# MISC.net
KiCad netlist of a schematic drawn in Altium Designer
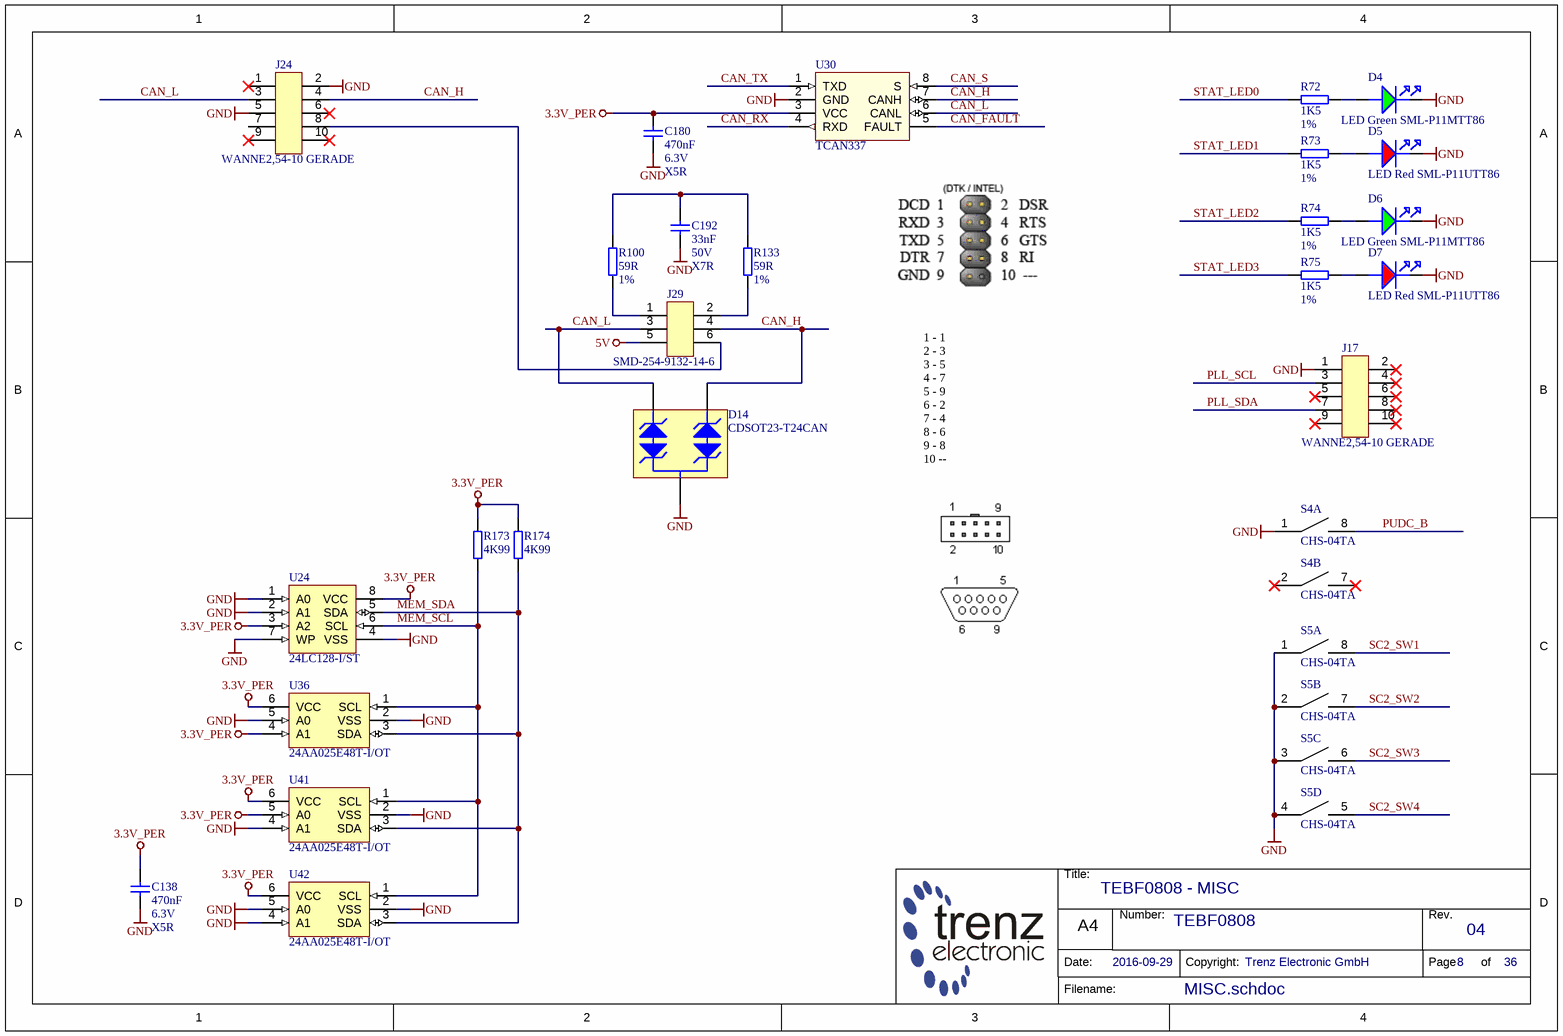
[diagram p0: MISC.schdoc]

(export (version "E")
  (design (tool "Eeschema 10.0.6"))
  (components
    (comp (ref "C138")
      (value "470nF")
      (footprint "CAPC1005X55N")
      (description "KON 470nF 6,3V X5R SMD")
      (fields (field (name "VOLTAGE") "6.3V") (field (name "TECHNOLOGY") "X5R"))
      (libsource (lib "TE") (part "CAP-NP"))
    )
    (comp (ref "C180")
      (value "470nF")
      (footprint "CAPC1005X55N")
      (description "KON 470nF 6,3V X5R SMD")
      (fields (field (name "VOLTAGE") "6.3V") (field (name "TECHNOLOGY") "X5R"))
      (libsource (lib "TE") (part "CAP-NP"))
    )
    (comp (ref "C192")
      (value "33nF")
      (footprint "CAPC1608X90N")
      (description "KON 33nF 50V X7R SMD 10%")
      (fields
        (field (name "VOLTAGE") "50V")
        (field (name "TECHNOLOGY") "X7R")
        (field (name "TOLERANCE") "10%")
      )
      (libsource (lib "TE") (part "CAP-NP"))
    )
    (comp (ref "D4")
      (value "LED Green SML-P11MTT86")
      (footprint "LEDC1006X25N_GREEN")
      (description "LED Grün SML-P11MTT86 SMD")
      (libsource (lib "TE") (part "LED_GRUEN"))
    )
    (comp (ref "D5")
      (value "LED Red SML-P11UTT86")
      (footprint "LEDC1006X25N_RED")
      (description "LED Rot SML-P11UTT86 SMD")
      (libsource (lib "TE") (part "LED_ROT"))
    )
    (comp (ref "D6")
      (value "LED Green SML-P11MTT86")
      (footprint "LEDC1006X25N_GREEN")
      (description "LED Grün SML-P11MTT86 SMD")
      (libsource (lib "TE") (part "LED_GRUEN"))
    )
    (comp (ref "D7")
      (value "LED Red SML-P11UTT86")
      (footprint "LEDC1006X25N_RED")
      (description "LED Rot SML-P11UTT86 SMD")
      (libsource (lib "TE") (part "LED_ROT"))
    )
    (comp (ref "D14")
      (value "CDSOT23-T24CAN")
      (footprint "SOT95P237X112-3N")
      (libsource (lib "TE") (part "SM712"))
    )
    (comp (ref "J17")
      (value "WANNE2,54-10 GERADE")
      (footprint "WANNE2,54-10 GERADE")
      (description "Stiftleiste Wanne 10polig")
      (libsource (lib "TE") (part "CON-10"))
    )
    (comp (ref "J24")
      (value "WANNE2,54-10 GERADE")
      (footprint "WANNE2,54-10 GERADE")
      (description "Stiftleiste Wanne 10polig")
      (libsource (lib "TE") (part "CON-10"))
    )
    (comp (ref "J29")
      (value "SMD-254-9132-14-6")
      (footprint "SMD-254-9132-14-6")
      (description "Stiftleiste gerade 2-reihig, 6pol. SMD")
      (libsource (lib "TE") (part "CON-6"))
    )
    (comp (ref "R72")
      (value "1K5")
      (footprint "RESC1005X40N")
      (description "WID SMD 1K5 1% 0,063W")
      (fields (field (name "TOLERANCE") "1%"))
      (libsource (lib "TE") (part "RES"))
    )
    (comp (ref "R73")
      (value "1K5")
      (footprint "RESC1005X40N")
      (description "WID SMD 1K5 1% 0,063W")
      (fields (field (name "TOLERANCE") "1%"))
      (libsource (lib "TE") (part "RES"))
    )
    (comp (ref "R74")
      (value "1K5")
      (footprint "RESC1005X40N")
      (description "WID SMD 1K5 1% 0,063W")
      (fields (field (name "TOLERANCE") "1%"))
      (libsource (lib "TE") (part "RES"))
    )
    (comp (ref "R75")
      (value "1K5")
      (footprint "RESC1005X40N")
      (description "WID SMD 1K5 1% 0,063W")
      (fields (field (name "TOLERANCE") "1%"))
      (libsource (lib "TE") (part "RES"))
    )
    (comp (ref "R100")
      (value "59R")
      (footprint "RESC6332X80N")
      (description "WID SMD 59R 2W 1%")
      (fields (field (name "TOLERANCE") "1%"))
      (libsource (lib "TE") (part "RES"))
    )
    (comp (ref "R133")
      (value "59R")
      (footprint "RESC6332X80N")
      (description "WID SMD 59R 2W 1%")
      (fields (field (name "TOLERANCE") "1%"))
      (libsource (lib "TE") (part "RES"))
    )
    (comp (ref "R173")
      (value "4K99")
      (footprint "RESC1005X40N")
      (description "WID SMD 4K99 1% 0,063W")
      (fields (field (name "TOLERANCE") "1%"))
      (libsource (lib "TE") (part "RES"))
    )
    (comp (ref "R174")
      (value "4K99")
      (footprint "RESC1005X40N")
      (description "WID SMD 4K99 1% 0,063W")
      (fields (field (name "TOLERANCE") "1%"))
      (libsource (lib "TE") (part "RES"))
    )
    (comp (ref "S4")
      (value "CHS-04TA")
      (footprint "CHS-04TA")
      (description "DIP Schalter 4 fach 1,27mm SMD")
      (libsource (lib "TE") (part "CHS-04TA"))
    )
    (comp (ref "S5")
      (value "CHS-04TA")
      (footprint "CHS-04TA")
      (description "DIP Schalter 4 fach 1,27mm SMD")
      (libsource (lib "TE") (part "CHS-04TA"))
    )
    (comp (ref "U24")
      (value "24LC128-I/ST")
      (footprint "SOP65P640X120-8N-MC")
      (libsource (lib "TE") (part "24LC128I"))
    )
    (comp (ref "U30")
      (value "TCAN337")
      (footprint "SOIC127P600X175-8N")
      (description "TCAN337GDR  CAN Transceivers")
      (libsource (lib "TE") (part "TCAN337"))
    )
    (comp (ref "U36")
      (value "24AA025E48T-I/OT")
      (footprint "SOT95P280X145-6N")
      (libsource (lib "TE") (part "24AA025E48"))
    )
    (comp (ref "U41")
      (value "24AA025E48T-I/OT")
      (footprint "SOT95P280X145-6N")
      (libsource (lib "TE") (part "24AA025E48"))
    )
    (comp (ref "U42")
      (value "24AA025E48T-I/OT")
      (footprint "SOT95P280X145-6N")
      (libsource (lib "TE") (part "24AA025E48"))
    )
  )
  (nets
    (net (code "1") (name "/CAN_FAULT") (class "Default")
      (node (ref "U30") (pin "5") (pinfunction "FAULT_5") (pintype "passive"))
    )
    (net (code "2") (name "/CAN_H") (class "Default")
      (node (ref "D14") (pin "1") (pinfunction "IO1_1") (pintype "passive"))
      (node (ref "J24") (pin "4") (pinfunction "4_4") (pintype "passive"))
      (node (ref "J29") (pin "4") (pintype "passive"))
      (node (ref "U30") (pin "7") (pinfunction "CANH_7") (pintype "bidirectional"))
    )
    (net (code "3") (name "/CAN_L") (class "Default")
      (node (ref "D14") (pin "2") (pinfunction "IO2_2") (pintype "passive"))
      (node (ref "J24") (pin "3") (pinfunction "3_3") (pintype "passive"))
      (node (ref "J29") (pin "3") (pintype "passive"))
      (node (ref "U30") (pin "6") (pinfunction "CANL_6") (pintype "bidirectional"))
    )
    (net (code "4") (name "/CAN_RX") (class "Default")
      (node (ref "U30") (pin "4") (pinfunction "RXD_4") (pintype "output"))
    )
    (net (code "5") (name "/CAN_S") (class "Default")
      (node (ref "U30") (pin "8") (pinfunction "S_8") (pintype "input"))
    )
    (net (code "6") (name "/CAN_TX") (class "Default")
      (node (ref "U30") (pin "1") (pinfunction "TXD_1") (pintype "input"))
    )
    (net (code "7") (name "/MEM_SCL") (class "Default")
      (node (ref "R173") (pin "2") (pinfunction "2_2") (pintype "passive"))
      (node (ref "U24") (pin "6") (pinfunction "SCL_6") (pintype "input"))
      (node (ref "U36") (pin "1") (pinfunction "SCL_1") (pintype "input"))
      (node (ref "U41") (pin "1") (pinfunction "SCL_1") (pintype "input"))
      (node (ref "U42") (pin "1") (pinfunction "SCL_1") (pintype "input"))
    )
    (net (code "8") (name "/MEM_SDA") (class "Default")
      (node (ref "R174") (pin "2") (pinfunction "2_2") (pintype "passive"))
      (node (ref "U24") (pin "5") (pinfunction "SDA_5") (pintype "bidirectional"))
      (node (ref "U36") (pin "3") (pinfunction "SDA_3") (pintype "bidirectional"))
      (node (ref "U41") (pin "3") (pinfunction "SDA_3") (pintype "bidirectional"))
      (node (ref "U42") (pin "3") (pinfunction "SDA_3") (pintype "bidirectional"))
    )
    (net (code "9") (name "/PLL_SCL") (class "Default")
      (node (ref "J17") (pin "3") (pinfunction "3_3") (pintype "passive"))
    )
    (net (code "10") (name "/PLL_SDA") (class "Default")
      (node (ref "J17") (pin "7") (pinfunction "7_7") (pintype "passive"))
    )
    (net (code "11") (name "/PUDC_B") (class "Default")
      (node (ref "S4") (pin "8") (pinfunction "8_8") (pintype "passive"))
    )
    (net (code "12") (name "/SC2_SW1") (class "Default")
      (node (ref "S5") (pin "8") (pinfunction "8_8") (pintype "passive"))
    )
    (net (code "13") (name "/SC2_SW2") (class "Default")
      (node (ref "S5") (pin "7") (pinfunction "7_7") (pintype "passive"))
    )
    (net (code "14") (name "/SC2_SW3") (class "Default")
      (node (ref "S5") (pin "6") (pinfunction "6_6") (pintype "passive"))
    )
    (net (code "15") (name "/SC2_SW4") (class "Default")
      (node (ref "S5") (pin "5") (pinfunction "5_5") (pintype "passive"))
    )
    (net (code "16") (name "/STAT_LED0") (class "Default")
      (node (ref "R72") (pin "1") (pinfunction "1_1") (pintype "passive"))
    )
    (net (code "17") (name "/STAT_LED1") (class "Default")
      (node (ref "R73") (pin "1") (pinfunction "1_1") (pintype "passive"))
    )
    (net (code "18") (name "/STAT_LED2") (class "Default")
      (node (ref "R74") (pin "1") (pinfunction "1_1") (pintype "passive"))
    )
    (net (code "19") (name "/STAT_LED3") (class "Default")
      (node (ref "R75") (pin "1") (pinfunction "1_1") (pintype "passive"))
    )
    (net (code "20") (name "3.3V_PER") (class "Default")
      (node (ref "C138") (pin "1") (pinfunction "1_1") (pintype "passive"))
      (node (ref "C180") (pin "2") (pinfunction "2_2") (pintype "passive"))
      (node (ref "R173") (pin "1") (pinfunction "1_1") (pintype "passive"))
      (node (ref "R174") (pin "1") (pinfunction "1_1") (pintype "passive"))
      (node (ref "U24") (pin "3") (pinfunction "A2_3") (pintype "input"))
      (node (ref "U24") (pin "8") (pinfunction "VCC_8") (pintype "power_in"))
      (node (ref "U30") (pin "3") (pinfunction "VCC_3") (pintype "power_in"))
      (node (ref "U36") (pin "4") (pinfunction "A1_4") (pintype "input"))
      (node (ref "U36") (pin "6") (pinfunction "VCC_6") (pintype "power_in"))
      (node (ref "U41") (pin "5") (pinfunction "A0_5") (pintype "input"))
      (node (ref "U41") (pin "6") (pinfunction "VCC_6") (pintype "power_in"))
      (node (ref "U42") (pin "6") (pinfunction "VCC_6") (pintype "power_in"))
    )
    (net (code "21") (name "5V") (class "Default") (node (ref "J29") (pin "5") (pintype "passive")))
    (net (code "22") (name "GND") (class "Default")
      (node (ref "C138") (pin "2") (pinfunction "2_2") (pintype "passive"))
      (node (ref "C180") (pin "1") (pinfunction "1_1") (pintype "passive"))
      (node (ref "C192") (pin "1") (pinfunction "1_1") (pintype "passive"))
      (node (ref "D14") (pin "3") (pinfunction "GND_3") (pintype "passive"))
      (node (ref "D4") (pin "K") (pinfunction "K_K") (pintype "passive"))
      (node (ref "D5") (pin "K") (pinfunction "K_K") (pintype "passive"))
      (node (ref "D6") (pin "K") (pinfunction "K_K") (pintype "passive"))
      (node (ref "D7") (pin "K") (pinfunction "K_K") (pintype "passive"))
      (node (ref "J17") (pin "1") (pinfunction "1_1") (pintype "passive"))
      (node (ref "J24") (pin "2") (pinfunction "2_2") (pintype "passive"))
      (node (ref "J24") (pin "5") (pinfunction "5_5") (pintype "passive"))
      (node (ref "S4") (pin "1") (pinfunction "1_1") (pintype "passive"))
      (node (ref "S5") (pin "1") (pinfunction "1_1") (pintype "passive"))
      (node (ref "S5") (pin "2") (pinfunction "2_2") (pintype "passive"))
      (node (ref "S5") (pin "3") (pinfunction "3_3") (pintype "passive"))
      (node (ref "S5") (pin "4") (pinfunction "4_4") (pintype "passive"))
      (node (ref "U24") (pin "1") (pinfunction "A0_1") (pintype "input"))
      (node (ref "U24") (pin "2") (pinfunction "A1_2") (pintype "input"))
      (node (ref "U24") (pin "4") (pinfunction "VSS_4") (pintype "power_in"))
      (node (ref "U24") (pin "7") (pinfunction "WP_7") (pintype "input"))
      (node (ref "U30") (pin "2") (pinfunction "GND_2") (pintype "power_in"))
      (node (ref "U36") (pin "2") (pinfunction "VSS_2") (pintype "power_in"))
      (node (ref "U36") (pin "5") (pinfunction "A0_5") (pintype "input"))
      (node (ref "U41") (pin "2") (pinfunction "VSS_2") (pintype "power_in"))
      (node (ref "U41") (pin "4") (pinfunction "A1_4") (pintype "input"))
      (node (ref "U42") (pin "2") (pinfunction "VSS_2") (pintype "power_in"))
      (node (ref "U42") (pin "4") (pinfunction "A1_4") (pintype "input"))
      (node (ref "U42") (pin "5") (pinfunction "A0_5") (pintype "input"))
    )
    (net (code "23") (name "Net-(C192-Pad2)") (class "Default")
      (node (ref "C192") (pin "2") (pinfunction "2_2") (pintype "passive"))
      (node (ref "R100") (pin "1") (pinfunction "1_1") (pintype "passive"))
      (node (ref "R133") (pin "1") (pinfunction "1_1") (pintype "passive"))
    )
    (net (code "24") (name "Net-(D4-PadA)") (class "Default")
      (node (ref "D4") (pin "A") (pinfunction "A_A") (pintype "passive"))
      (node (ref "R72") (pin "2") (pinfunction "2_2") (pintype "passive"))
    )
    (net (code "25") (name "Net-(D5-PadA)") (class "Default")
      (node (ref "D5") (pin "A") (pinfunction "A_A") (pintype "passive"))
      (node (ref "R73") (pin "2") (pinfunction "2_2") (pintype "passive"))
    )
    (net (code "26") (name "Net-(D6-PadA)") (class "Default")
      (node (ref "D6") (pin "A") (pinfunction "A_A") (pintype "passive"))
      (node (ref "R74") (pin "2") (pinfunction "2_2") (pintype "passive"))
    )
    (net (code "27") (name "Net-(D7-PadA)") (class "Default")
      (node (ref "D7") (pin "A") (pinfunction "A_A") (pintype "passive"))
      (node (ref "R75") (pin "2") (pinfunction "2_2") (pintype "passive"))
    )
    (net (code "28") (name "Net-(J24-Pad8)") (class "Default")
      (node (ref "J24") (pin "8") (pinfunction "8_8") (pintype "passive"))
      (node (ref "J29") (pin "6") (pintype "passive"))
    )
    (net (code "29") (name "Net-(J29-Pad1)") (class "Default")
      (node (ref "J29") (pin "1") (pintype "passive"))
      (node (ref "R100") (pin "2") (pinfunction "2_2") (pintype "passive"))
    )
    (net (code "30") (name "Net-(J29-Pad2)") (class "Default")
      (node (ref "J29") (pin "2") (pintype "passive"))
      (node (ref "R133") (pin "2") (pinfunction "2_2") (pintype "passive"))
    )
    (net (code "31") (name "unconnected-(J17-Pad2)") (class "Default")
      (node (ref "J17") (pin "2") (pinfunction "2_2") (pintype "passive+no_connect"))
    )
    (net (code "32") (name "unconnected-(J17-Pad4)") (class "Default")
      (node (ref "J17") (pin "4") (pinfunction "4_4") (pintype "passive+no_connect"))
    )
    (net (code "33") (name "unconnected-(J17-Pad5)") (class "Default")
      (node (ref "J17") (pin "5") (pinfunction "5_5") (pintype "passive+no_connect"))
    )
    (net (code "34") (name "unconnected-(J17-Pad6)") (class "Default")
      (node (ref "J17") (pin "6") (pinfunction "6_6") (pintype "passive+no_connect"))
    )
    (net (code "35") (name "unconnected-(J17-Pad8)") (class "Default")
      (node (ref "J17") (pin "8") (pinfunction "8_8") (pintype "passive+no_connect"))
    )
    (net (code "36") (name "unconnected-(J17-Pad9)") (class "Default")
      (node (ref "J17") (pin "9") (pinfunction "9_9") (pintype "passive+no_connect"))
    )
    (net (code "37") (name "unconnected-(J17-Pad10)") (class "Default")
      (node (ref "J17") (pin "10") (pinfunction "10_10") (pintype "passive+no_connect"))
    )
    (net (code "38") (name "unconnected-(J24-Pad1)") (class "Default")
      (node (ref "J24") (pin "1") (pinfunction "1_1") (pintype "passive+no_connect"))
    )
    (net (code "39") (name "unconnected-(J24-Pad6)") (class "Default")
      (node (ref "J24") (pin "6") (pinfunction "6_6") (pintype "passive+no_connect"))
    )
    (net (code "40") (name "unconnected-(J24-Pad7)") (class "Default")
      (node (ref "J24") (pin "7") (pinfunction "7_7") (pintype "passive"))
    )
    (net (code "41") (name "unconnected-(J24-Pad9)") (class "Default")
      (node (ref "J24") (pin "9") (pinfunction "9_9") (pintype "passive+no_connect"))
    )
    (net (code "42") (name "unconnected-(J24-Pad10)") (class "Default")
      (node (ref "J24") (pin "10") (pinfunction "10_10") (pintype "passive+no_connect"))
    )
    (net (code "43") (name "unconnected-(S4-Pad2)") (class "Default")
      (node (ref "S4") (pin "2") (pinfunction "2_2") (pintype "passive+no_connect"))
    )
    (net (code "44") (name "unconnected-(S4-Pad7)") (class "Default")
      (node (ref "S4") (pin "7") (pinfunction "7_7") (pintype "passive+no_connect"))
    )
  )
)
